# Sch1.net
KiCad netlist of a schematic drawn in Altium Designer
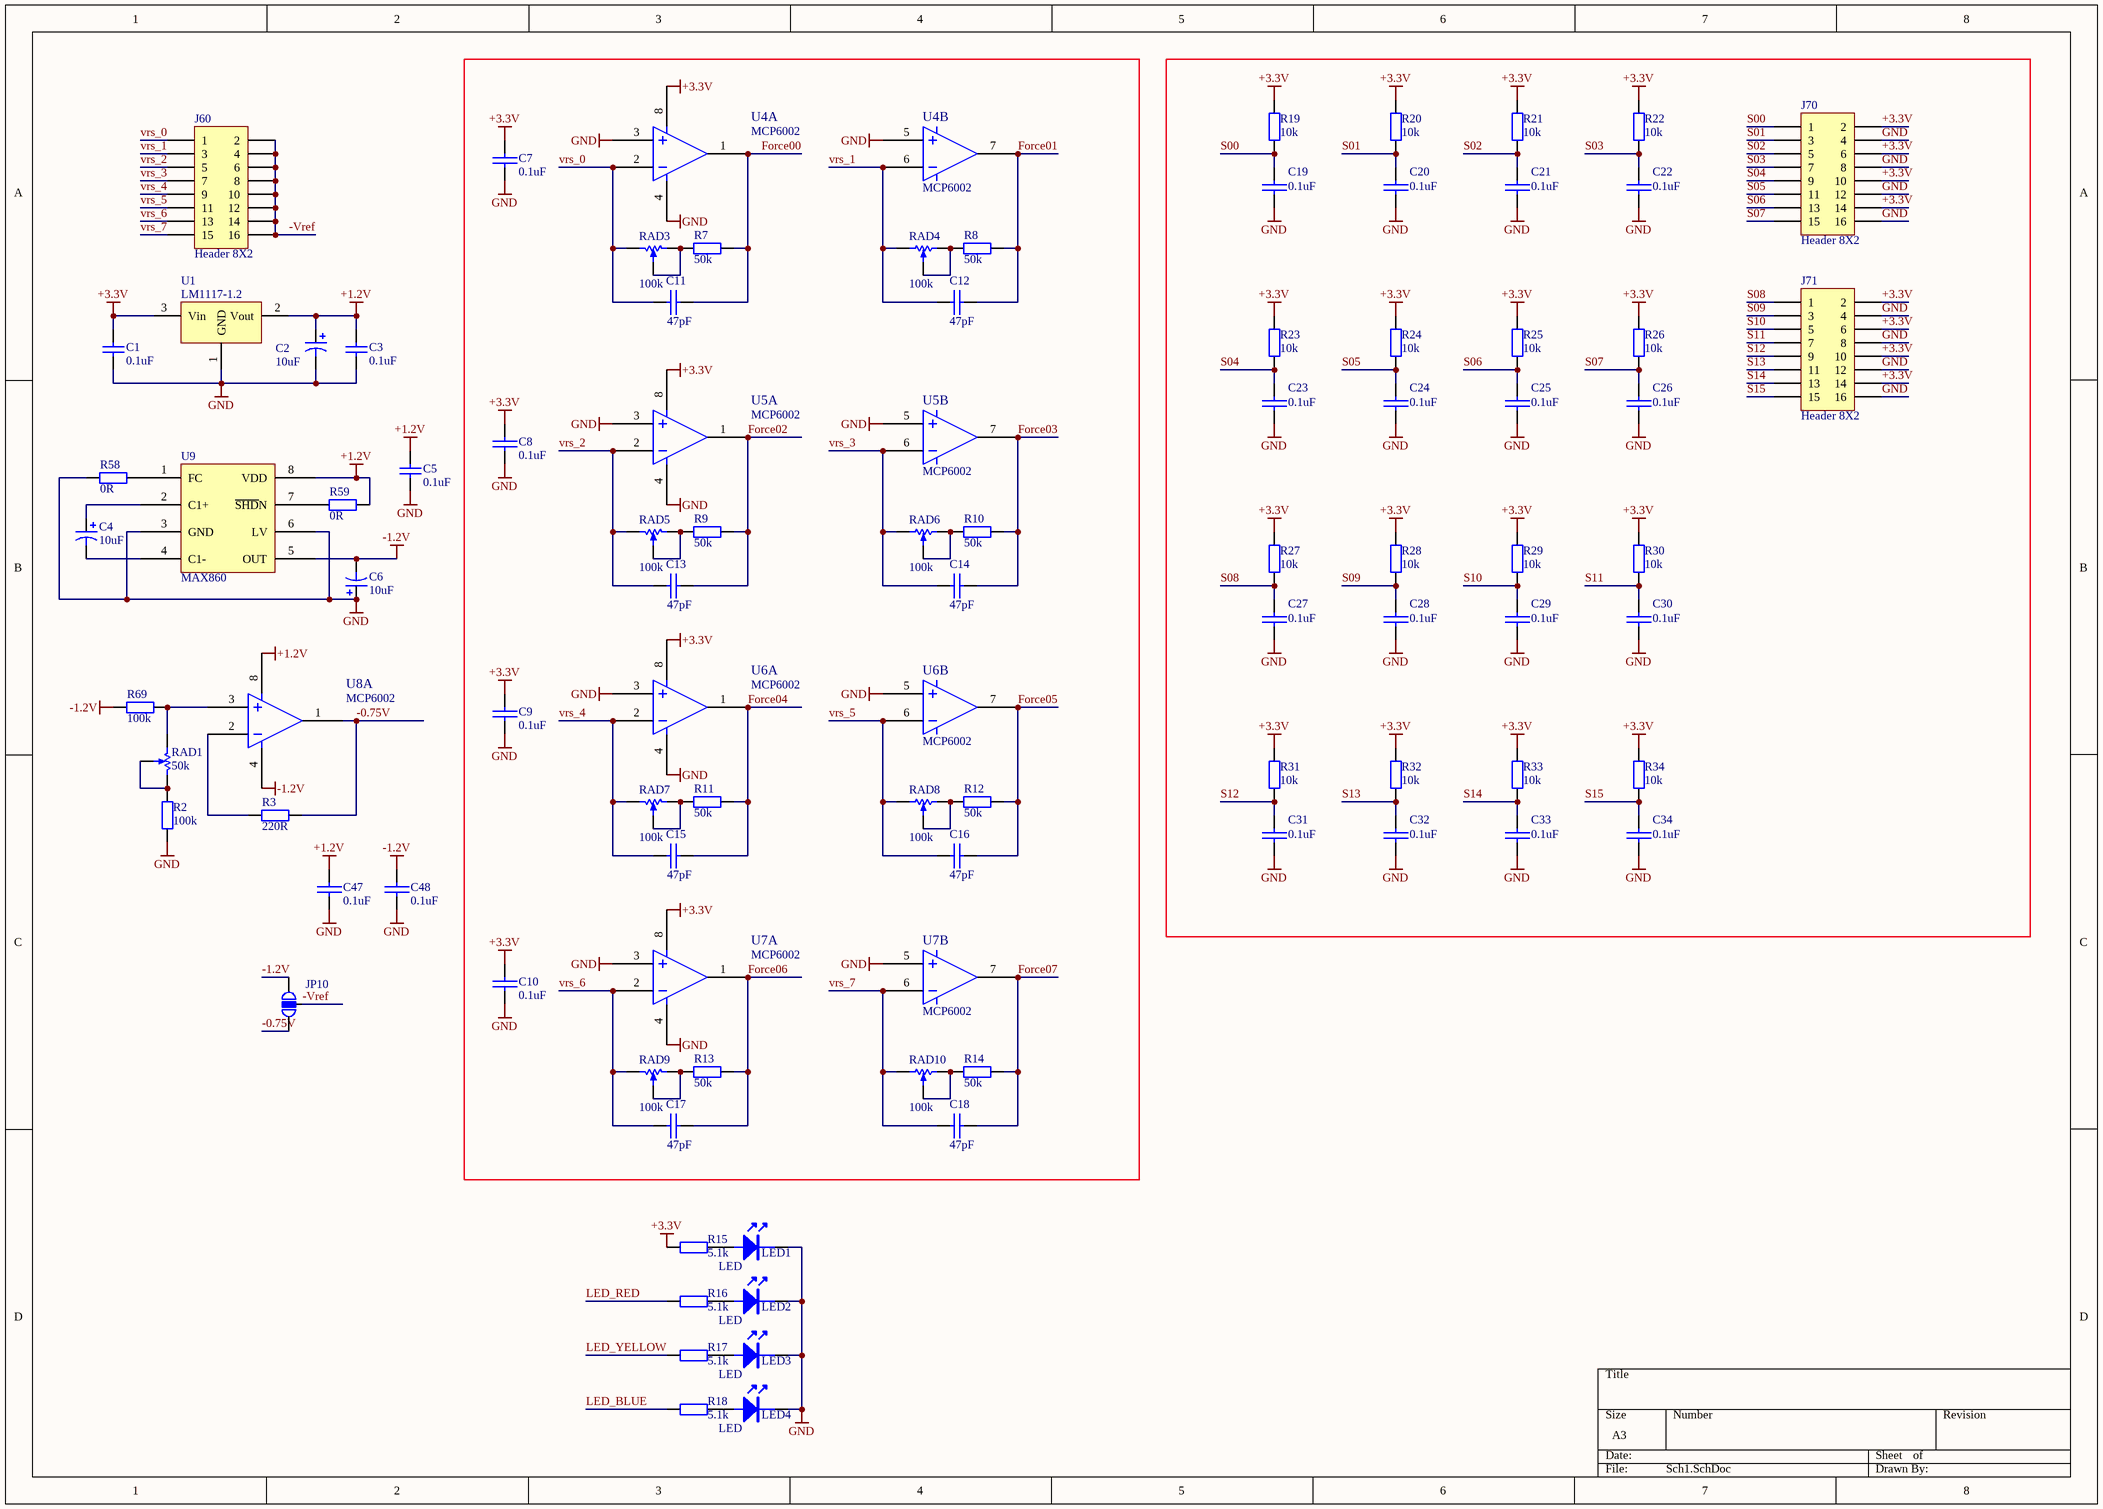
[diagram p0: Sch1.SchDoc]

(export (version "E")
  (design (tool "Eeschema 10.0.6"))
  (components
    (comp (ref "C1")
      (value "0.1uF")
      (footprint "CC0603")
      (description "贴片电容")
      (fields (field (name "Comment") "0603-50V-0.1uF"))
      (libsource (lib "Miscellaneous Devices") (part "Cap"))
    )
    (comp (ref "C2")
      (value "10uF")
      (footprint "SMD-EC-F5")
      (description "贴片铝电解电容")
      (fields (field (name "Comment") "CD-50V-10uF-F5(SMD)"))
      (libsource (lib "Miscellaneous Devices") (part "Cap Pol1"))
    )
    (comp (ref "C3")
      (value "0.1uF")
      (footprint "CC0603")
      (description "贴片电容")
      (fields (field (name "Comment") "0603-50V-0.1uF"))
      (libsource (lib "Miscellaneous Devices") (part "Cap"))
    )
    (comp (ref "C4")
      (value "10uF")
      (footprint "SMD-EC-F5")
      (description "贴片铝电解电容")
      (fields (field (name "Comment") "CD-50V-10uF-F5(SMD)"))
      (libsource (lib "Miscellaneous Devices") (part "Cap Pol1"))
    )
    (comp (ref "C5")
      (value "0.1uF")
      (footprint "CC0603")
      (description "贴片电容")
      (fields (field (name "Comment") "0603-50V-0.1uF"))
      (libsource (lib "Miscellaneous Devices") (part "Cap"))
    )
    (comp (ref "C6")
      (value "10uF")
      (footprint "SMD-EC-F5")
      (description "贴片铝电解电容")
      (fields (field (name "Comment") "CD-50V-10uF-F5(SMD)"))
      (libsource (lib "Miscellaneous Devices") (part "Cap Pol1"))
    )
    (comp (ref "C7")
      (value "0.1uF")
      (footprint "CC0603")
      (description "贴片电容")
      (fields (field (name "Comment") "0603-50V-0.1uF"))
      (libsource (lib "*") (part "CAP"))
    )
    (comp (ref "C8")
      (value "0.1uF")
      (footprint "CC0603")
      (description "贴片电容")
      (fields (field (name "Comment") "0603-50V-0.1uF"))
      (libsource (lib "*") (part "CAP"))
    )
    (comp (ref "C9")
      (value "0.1uF")
      (footprint "CC0603")
      (description "贴片电容")
      (fields (field (name "Comment") "0603-50V-0.1uF"))
      (libsource (lib "*") (part "CAP"))
    )
    (comp (ref "C10")
      (value "0.1uF")
      (footprint "CC0603")
      (description "贴片电容")
      (fields (field (name "Comment") "0603-50V-0.1uF"))
      (libsource (lib "*") (part "CAP"))
    )
    (comp (ref "C11")
      (value "47pF")
      (footprint "CC0603")
      (description "贴片电容")
      (fields (field (name "Comment") "0603-50V-47pF"))
      (libsource (lib "*") (part "CAP"))
    )
    (comp (ref "C12")
      (value "47pF")
      (footprint "CC0603")
      (description "贴片电容")
      (fields (field (name "Comment") "0603-50V-47pF"))
      (libsource (lib "*") (part "CAP"))
    )
    (comp (ref "C13")
      (value "47pF")
      (footprint "CC0603")
      (description "贴片电容")
      (fields (field (name "Comment") "0603-50V-47pF"))
      (libsource (lib "*") (part "CAP"))
    )
    (comp (ref "C14")
      (value "47pF")
      (footprint "CC0603")
      (description "贴片电容")
      (fields (field (name "Comment") "0603-50V-47pF"))
      (libsource (lib "*") (part "CAP"))
    )
    (comp (ref "C15")
      (value "47pF")
      (footprint "CC0603")
      (description "贴片电容")
      (fields (field (name "Comment") "0603-50V-47pF"))
      (libsource (lib "*") (part "CAP"))
    )
    (comp (ref "C16")
      (value "47pF")
      (footprint "CC0603")
      (description "贴片电容")
      (fields (field (name "Comment") "0603-50V-47pF"))
      (libsource (lib "*") (part "CAP"))
    )
    (comp (ref "C17")
      (value "47pF")
      (footprint "CC0603")
      (description "贴片电容")
      (fields (field (name "Comment") "0603-50V-47pF"))
      (libsource (lib "*") (part "CAP"))
    )
    (comp (ref "C18")
      (value "47pF")
      (footprint "CC0603")
      (description "贴片电容")
      (fields (field (name "Comment") "0603-50V-47pF"))
      (libsource (lib "*") (part "CAP"))
    )
    (comp (ref "C19")
      (value "0.1uF")
      (footprint "CC0603")
      (description "贴片电容")
      (fields (field (name "Comment") "0603-50V-0.1uF"))
      (libsource (lib "*") (part "CAP"))
    )
    (comp (ref "C20")
      (value "0.1uF")
      (footprint "CC0603")
      (description "贴片电容")
      (fields (field (name "Comment") "0603-50V-0.1uF"))
      (libsource (lib "*") (part "CAP"))
    )
    (comp (ref "C21")
      (value "0.1uF")
      (footprint "CC0603")
      (description "贴片电容")
      (fields (field (name "Comment") "0603-50V-0.1uF"))
      (libsource (lib "*") (part "CAP"))
    )
    (comp (ref "C22")
      (value "0.1uF")
      (footprint "CC0603")
      (description "贴片电容")
      (fields (field (name "Comment") "0603-50V-0.1uF"))
      (libsource (lib "*") (part "CAP"))
    )
    (comp (ref "C23")
      (value "0.1uF")
      (footprint "CC0603")
      (description "贴片电容")
      (fields (field (name "Comment") "0603-50V-0.1uF"))
      (libsource (lib "*") (part "CAP"))
    )
    (comp (ref "C24")
      (value "0.1uF")
      (footprint "CC0603")
      (description "贴片电容")
      (fields (field (name "Comment") "0603-50V-0.1uF"))
      (libsource (lib "*") (part "CAP"))
    )
    (comp (ref "C25")
      (value "0.1uF")
      (footprint "CC0603")
      (description "贴片电容")
      (fields (field (name "Comment") "0603-50V-0.1uF"))
      (libsource (lib "*") (part "CAP"))
    )
    (comp (ref "C26")
      (value "0.1uF")
      (footprint "CC0603")
      (description "贴片电容")
      (fields (field (name "Comment") "0603-50V-0.1uF"))
      (libsource (lib "*") (part "CAP"))
    )
    (comp (ref "C27")
      (value "0.1uF")
      (footprint "CC0603")
      (description "贴片电容")
      (fields (field (name "Comment") "0603-50V-0.1uF"))
      (libsource (lib "*") (part "CAP"))
    )
    (comp (ref "C28")
      (value "0.1uF")
      (footprint "CC0603")
      (description "贴片电容")
      (fields (field (name "Comment") "0603-50V-0.1uF"))
      (libsource (lib "*") (part "CAP"))
    )
    (comp (ref "C29")
      (value "0.1uF")
      (footprint "CC0603")
      (description "贴片电容")
      (fields (field (name "Comment") "0603-50V-0.1uF"))
      (libsource (lib "*") (part "CAP"))
    )
    (comp (ref "C30")
      (value "0.1uF")
      (footprint "CC0603")
      (description "贴片电容")
      (fields (field (name "Comment") "0603-50V-0.1uF"))
      (libsource (lib "*") (part "CAP"))
    )
    (comp (ref "C31")
      (value "0.1uF")
      (footprint "CC0603")
      (description "贴片电容")
      (fields (field (name "Comment") "0603-50V-0.1uF"))
      (libsource (lib "*") (part "CAP"))
    )
    (comp (ref "C32")
      (value "0.1uF")
      (footprint "CC0603")
      (description "贴片电容")
      (fields (field (name "Comment") "0603-50V-0.1uF"))
      (libsource (lib "*") (part "CAP"))
    )
    (comp (ref "C33")
      (value "0.1uF")
      (footprint "CC0603")
      (description "贴片电容")
      (fields (field (name "Comment") "0603-50V-0.1uF"))
      (libsource (lib "*") (part "CAP"))
    )
    (comp (ref "C34")
      (value "0.1uF")
      (footprint "CC0603")
      (description "贴片电容")
      (fields (field (name "Comment") "0603-50V-0.1uF"))
      (libsource (lib "*") (part "CAP"))
    )
    (comp (ref "C47")
      (value "0.1uF")
      (footprint "CC0603")
      (description "贴片电容")
      (fields (field (name "Comment") "0603-50V-0.1uF"))
      (libsource (lib "*") (part "CAP"))
    )
    (comp (ref "C48")
      (value "0.1uF")
      (footprint "CC0603")
      (description "贴片电容")
      (fields (field (name "Comment") "0603-50V-0.1uF"))
      (libsource (lib "*") (part "CAP"))
    )
    (comp (ref "J60")
      (value "Header 8X2")
      (footprint "HDR2X8")
      (description "排针")
      (libsource (lib "Miscellaneous Connectors") (part "Header 8X2"))
    )
    (comp (ref "J70")
      (value "Header 8X2")
      (footprint "HDR2X8")
      (description "排针")
      (libsource (lib "Miscellaneous Connectors") (part "Header 8X2"))
    )
    (comp (ref "J71")
      (value "Header 8X2")
      (footprint "HDR2X8")
      (description "排针")
      (libsource (lib "Miscellaneous Connectors") (part "Header 8X2"))
    )
    (comp (ref "JP10") (value "Jumper") (footprint "HDR1X3") (libsource (lib "SHIELD_3") (part "Bell")))
    (comp (ref "LED1")
      (value "LED")
      (footprint "LED-R3")
      (description "发光二极管")
      (fields (field (name "Comment") "LED-φ3(翠绿)"))
      (libsource (lib "*") (part "LED"))
    )
    (comp (ref "LED2")
      (value "LED")
      (footprint "LED-R3")
      (description "发光二极管")
      (fields (field (name "Comment") "LED-φ3(红)"))
      (libsource (lib "*") (part "LED"))
    )
    (comp (ref "LED3")
      (value "LED")
      (footprint "LED-R3")
      (description "发光二极管")
      (fields (field (name "Comment") "LED-φ3(黄)"))
      (libsource (lib "*") (part "LED"))
    )
    (comp (ref "LED4")
      (value "LED")
      (footprint "LED-R3")
      (description "发光二极管")
      (fields (field (name "Comment") "LED-φ3(蓝)"))
      (libsource (lib "*") (part "LED"))
    )
    (comp (ref "R2")
      (value "100k")
      (footprint "0603")
      (description "贴片电阻")
      (fields (field (name "Comment") "0603-100kΩ±1％"))
      (libsource (lib "") (part "Res2_3"))
    )
    (comp (ref "R3")
      (value "220R")
      (footprint "0603")
      (description "贴片电阻")
      (fields (field (name "Comment") "0603-220Ω±1％"))
      (libsource (lib "Miscellaneous Devices") (part "Res2"))
    )
    (comp (ref "R7")
      (value "50k")
      (footprint "0603")
      (description "贴片电阻")
      (fields (field (name "Comment") "0603-50kΩ±1％"))
      (libsource (lib "Miscellaneous Devices") (part "Res2"))
    )
    (comp (ref "R8")
      (value "50k")
      (footprint "0603")
      (description "贴片电阻")
      (fields (field (name "Comment") "0603-50kΩ±1％"))
      (libsource (lib "") (part "Res2_2"))
    )
    (comp (ref "R9")
      (value "50k")
      (footprint "0603")
      (description "贴片电阻")
      (fields (field (name "Comment") "0603-50kΩ±1％"))
      (libsource (lib "Miscellaneous Devices") (part "Res2"))
    )
    (comp (ref "R10")
      (value "50k")
      (footprint "0603")
      (description "贴片电阻")
      (fields (field (name "Comment") "0603-50kΩ±1％"))
      (libsource (lib "") (part "Res2_2"))
    )
    (comp (ref "R11")
      (value "50k")
      (footprint "0603")
      (description "贴片电阻")
      (fields (field (name "Comment") "0603-50kΩ±1％"))
      (libsource (lib "Miscellaneous Devices") (part "Res2"))
    )
    (comp (ref "R12")
      (value "50k")
      (footprint "0603")
      (description "贴片电阻")
      (fields (field (name "Comment") "0603-50kΩ±1％"))
      (libsource (lib "") (part "Res2_2"))
    )
    (comp (ref "R13")
      (value "50k")
      (footprint "0603")
      (description "贴片电阻")
      (fields (field (name "Comment") "0603-50kΩ±1％"))
      (libsource (lib "Miscellaneous Devices") (part "Res2"))
    )
    (comp (ref "R14")
      (value "50k")
      (footprint "0603")
      (description "贴片电阻")
      (fields (field (name "Comment") "0603-50kΩ±1％"))
      (libsource (lib "") (part "Res2_2"))
    )
    (comp (ref "R15")
      (value "5.1k")
      (footprint "0603")
      (description "贴片电阻器")
      (fields (field (name "Comment") "0603-5.1kΩ±1％"))
      (libsource (lib "") (part "Res2_2"))
    )
    (comp (ref "R16")
      (value "5.1k")
      (footprint "0603")
      (description "贴片电阻器")
      (fields (field (name "Comment") "0603-5.1kΩ±1％"))
      (libsource (lib "") (part "Res2_2"))
    )
    (comp (ref "R17")
      (value "5.1k")
      (footprint "0603")
      (description "贴片电阻器")
      (fields (field (name "Comment") "0603-5.1kΩ±1％"))
      (libsource (lib "") (part "Res2_2"))
    )
    (comp (ref "R18")
      (value "5.1k")
      (footprint "0603")
      (description "贴片电阻器")
      (fields (field (name "Comment") "0603-5.1kΩ±1％"))
      (libsource (lib "") (part "Res2_2"))
    )
    (comp (ref "R19")
      (value "10k")
      (footprint "0603")
      (description "贴片电阻")
      (fields (field (name "Comment") "0603-10kΩ±1％"))
      (libsource (lib "") (part "Res2_1"))
    )
    (comp (ref "R20")
      (value "10k")
      (footprint "0603")
      (description "贴片电阻")
      (fields (field (name "Comment") "0603-10kΩ±1％"))
      (libsource (lib "") (part "Res2_1"))
    )
    (comp (ref "R21")
      (value "10k")
      (footprint "0603")
      (description "贴片电阻")
      (fields (field (name "Comment") "0603-10kΩ±1％"))
      (libsource (lib "") (part "Res2_1"))
    )
    (comp (ref "R22")
      (value "10k")
      (footprint "0603")
      (description "贴片电阻")
      (fields (field (name "Comment") "0603-10kΩ±1％"))
      (libsource (lib "") (part "Res2_1"))
    )
    (comp (ref "R23")
      (value "10k")
      (footprint "0603")
      (description "贴片电阻")
      (fields (field (name "Comment") "0603-10kΩ±1％"))
      (libsource (lib "") (part "Res2_1"))
    )
    (comp (ref "R24")
      (value "10k")
      (footprint "0603")
      (description "贴片电阻")
      (fields (field (name "Comment") "0603-10kΩ±1％"))
      (libsource (lib "") (part "Res2_1"))
    )
    (comp (ref "R25")
      (value "10k")
      (footprint "0603")
      (description "贴片电阻")
      (fields (field (name "Comment") "0603-10kΩ±1％"))
      (libsource (lib "") (part "Res2_1"))
    )
    (comp (ref "R26")
      (value "10k")
      (footprint "0603")
      (description "贴片电阻")
      (fields (field (name "Comment") "0603-10kΩ±1％"))
      (libsource (lib "") (part "Res2_1"))
    )
    (comp (ref "R27")
      (value "10k")
      (footprint "0603")
      (description "贴片电阻")
      (fields (field (name "Comment") "0603-10kΩ±1％"))
      (libsource (lib "") (part "Res2_1"))
    )
    (comp (ref "R28")
      (value "10k")
      (footprint "0603")
      (description "贴片电阻")
      (fields (field (name "Comment") "0603-10kΩ±1％"))
      (libsource (lib "") (part "Res2_1"))
    )
    (comp (ref "R29")
      (value "10k")
      (footprint "0603")
      (description "贴片电阻")
      (fields (field (name "Comment") "0603-10kΩ±1％"))
      (libsource (lib "") (part "Res2_1"))
    )
    (comp (ref "R30")
      (value "10k")
      (footprint "0603")
      (description "贴片电阻")
      (fields (field (name "Comment") "0603-10kΩ±1％"))
      (libsource (lib "") (part "Res2_1"))
    )
    (comp (ref "R31")
      (value "10k")
      (footprint "0603")
      (description "贴片电阻")
      (fields (field (name "Comment") "0603-10kΩ±1％"))
      (libsource (lib "") (part "Res2_1"))
    )
    (comp (ref "R32")
      (value "10k")
      (footprint "0603")
      (description "贴片电阻")
      (fields (field (name "Comment") "0603-10kΩ±1％"))
      (libsource (lib "") (part "Res2_1"))
    )
    (comp (ref "R33")
      (value "10k")
      (footprint "0603")
      (description "贴片电阻")
      (fields (field (name "Comment") "0603-10kΩ±1％"))
      (libsource (lib "") (part "Res2_1"))
    )
    (comp (ref "R34")
      (value "10k")
      (footprint "0603")
      (description "贴片电阻")
      (fields (field (name "Comment") "0603-10kΩ±1％"))
      (libsource (lib "") (part "Res2_1"))
    )
    (comp (ref "R58")
      (value "0R")
      (footprint "0603")
      (description "贴片电阻")
      (fields (field (name "Comment") "0603-0Ω±1％"))
      (libsource (lib "Miscellaneous Devices") (part "Res2"))
    )
    (comp (ref "R59")
      (value "0R")
      (footprint "0603")
      (description "贴片电阻")
      (fields (field (name "Comment") "0603-0Ω±1％"))
      (libsource (lib "Miscellaneous Devices") (part "Res2"))
    )
    (comp (ref "R69")
      (value "100k")
      (footprint "0603")
      (description "贴片电阻")
      (fields (field (name "Comment") "0603-100kΩ±1％"))
      (libsource (lib "") (part "Res2_1"))
    )
    (comp (ref "RAD1")
      (value "50k")
      (footprint "3224W")
      (description "贴片电位器")
      (fields (field (name "Comment") "3224W-50k"))
      (libsource (lib "Miscellaneous Devices") (part "RPot SM"))
    )
    (comp (ref "RAD3")
      (value "100k")
      (footprint "3224W")
      (description "贴片电位器")
      (fields (field (name "Comment") "3224W-100k"))
      (libsource (lib "Miscellaneous Devices") (part "RPot SM"))
    )
    (comp (ref "RAD4")
      (value "100k")
      (footprint "3224W")
      (description "贴片电位器")
      (fields (field (name "Comment") "3224W-100k"))
      (libsource (lib "Miscellaneous Devices") (part "RPot SM"))
    )
    (comp (ref "RAD5")
      (value "100k")
      (footprint "3224W")
      (description "贴片电位器")
      (fields (field (name "Comment") "3224W-100k"))
      (libsource (lib "Miscellaneous Devices") (part "RPot SM"))
    )
    (comp (ref "RAD6")
      (value "100k")
      (footprint "3224W")
      (description "贴片电位器")
      (fields (field (name "Comment") "3224W-100k"))
      (libsource (lib "Miscellaneous Devices") (part "RPot SM"))
    )
    (comp (ref "RAD7")
      (value "100k")
      (footprint "3224W")
      (description "贴片电位器")
      (fields (field (name "Comment") "3224W-100k"))
      (libsource (lib "Miscellaneous Devices") (part "RPot SM"))
    )
    (comp (ref "RAD8")
      (value "100k")
      (footprint "3224W")
      (description "贴片电位器")
      (fields (field (name "Comment") "3224W-100k"))
      (libsource (lib "Miscellaneous Devices") (part "RPot SM"))
    )
    (comp (ref "RAD9")
      (value "100k")
      (footprint "3224W")
      (description "贴片电位器")
      (fields (field (name "Comment") "3224W-100k"))
      (libsource (lib "Miscellaneous Devices") (part "RPot SM"))
    )
    (comp (ref "RAD10")
      (value "100k")
      (footprint "3224W")
      (description "贴片电位器")
      (fields (field (name "Comment") "3224W-100k"))
      (libsource (lib "Miscellaneous Devices") (part "RPot SM"))
    )
    (comp (ref "U1")
      (value "LM1117-1.2")
      (footprint "SOT223")
      (description "三端稳压器")
      (fields (field (name "Comment") "LM1117GS-1.2"))
      (libsource (lib "*") (part "78M05"))
    )
    (comp (ref "U4")
      (value "MCP6002")
      (footprint "SO-8")
      (description "集成电路")
      (libsource (lib "*") (part "1458"))
    )
    (comp (ref "U5")
      (value "MCP6002")
      (footprint "SO-8")
      (description "集成电路")
      (libsource (lib "*") (part "1458"))
    )
    (comp (ref "U6")
      (value "MCP6002")
      (footprint "SO-8")
      (description "集成电路")
      (libsource (lib "*") (part "1458"))
    )
    (comp (ref "U7")
      (value "MCP6002")
      (footprint "SO-8")
      (description "集成电路")
      (libsource (lib "*") (part "1458"))
    )
    (comp (ref "U8")
      (value "MCP6002")
      (footprint "SO-8")
      (description "集成电路")
      (libsource (lib "*") (part "1458"))
    )
    (comp (ref "U9")
      (value "MAX860")
      (footprint "SO-8")
      (description "集成电路")
      (fields (field (name "Comment") "max860"))
      (libsource (lib "Schlib1") (part "max860"))
    )
  )
  (nets
    (net (code "1") (name "+1.2V") (class "Default")
      (node (ref "C2") (pin "1") (pinfunction "1_1") (pintype "passive"))
      (node (ref "C3") (pin "2") (pinfunction "2_2") (pintype "passive"))
      (node (ref "C47") (pin "2") (pinfunction "2_2") (pintype "passive"))
      (node (ref "C5") (pin "2") (pinfunction "2_2") (pintype "passive"))
      (node (ref "R59") (pin "2") (pinfunction "2_2") (pintype "passive"))
      (node (ref "U1") (pin "2") (pinfunction "Vout_2") (pintype "passive"))
      (node (ref "U8") (pin "8") (pintype "passive"))
      (node (ref "U9") (pin "8") (pinfunction "VDD_8") (pintype "passive"))
    )
    (net (code "2") (name "+3.3V") (class "Default")
      (node (ref "C1") (pin "2") (pinfunction "2_2") (pintype "passive"))
      (node (ref "C10") (pin "2") (pinfunction "2_2") (pintype "passive"))
      (node (ref "C7") (pin "2") (pinfunction "2_2") (pintype "passive"))
      (node (ref "C8") (pin "2") (pinfunction "2_2") (pintype "passive"))
      (node (ref "C9") (pin "2") (pinfunction "2_2") (pintype "passive"))
      (node (ref "J70") (pin "10") (pinfunction "10_10") (pintype "passive"))
      (node (ref "J70") (pin "14") (pinfunction "14_14") (pintype "passive"))
      (node (ref "J70") (pin "2") (pinfunction "2_2") (pintype "passive"))
      (node (ref "J70") (pin "6") (pinfunction "6_6") (pintype "passive"))
      (node (ref "J71") (pin "10") (pinfunction "10_10") (pintype "passive"))
      (node (ref "J71") (pin "14") (pinfunction "14_14") (pintype "passive"))
      (node (ref "J71") (pin "2") (pinfunction "2_2") (pintype "passive"))
      (node (ref "J71") (pin "6") (pinfunction "6_6") (pintype "passive"))
      (node (ref "R15") (pin "2") (pinfunction "2_2") (pintype "passive"))
      (node (ref "R19") (pin "1") (pinfunction "1_1") (pintype "passive"))
      (node (ref "R20") (pin "1") (pinfunction "1_1") (pintype "passive"))
      (node (ref "R21") (pin "1") (pinfunction "1_1") (pintype "passive"))
      (node (ref "R22") (pin "1") (pinfunction "1_1") (pintype "passive"))
      (node (ref "R23") (pin "1") (pinfunction "1_1") (pintype "passive"))
      (node (ref "R24") (pin "1") (pinfunction "1_1") (pintype "passive"))
      (node (ref "R25") (pin "1") (pinfunction "1_1") (pintype "passive"))
      (node (ref "R26") (pin "1") (pinfunction "1_1") (pintype "passive"))
      (node (ref "R27") (pin "1") (pinfunction "1_1") (pintype "passive"))
      (node (ref "R28") (pin "1") (pinfunction "1_1") (pintype "passive"))
      (node (ref "R29") (pin "1") (pinfunction "1_1") (pintype "passive"))
      (node (ref "R30") (pin "1") (pinfunction "1_1") (pintype "passive"))
      (node (ref "R31") (pin "1") (pinfunction "1_1") (pintype "passive"))
      (node (ref "R32") (pin "1") (pinfunction "1_1") (pintype "passive"))
      (node (ref "R33") (pin "1") (pinfunction "1_1") (pintype "passive"))
      (node (ref "R34") (pin "1") (pinfunction "1_1") (pintype "passive"))
      (node (ref "U1") (pin "3") (pinfunction "Vin_3") (pintype "passive"))
      (node (ref "U4") (pin "8") (pintype "passive"))
      (node (ref "U5") (pin "8") (pintype "passive"))
      (node (ref "U6") (pin "8") (pintype "passive"))
      (node (ref "U7") (pin "8") (pintype "passive"))
    )
    (net (code "3") (name "-1.2V") (class "Default")
      (node (ref "C48") (pin "2") (pinfunction "2_2") (pintype "passive"))
      (node (ref "C6") (pin "2") (pinfunction "2_2") (pintype "passive"))
      (node (ref "JP10") (pin "1") (pinfunction "A_1") (pintype "passive"))
      (node (ref "R69") (pin "2") (pinfunction "2_2") (pintype "passive"))
      (node (ref "U8") (pin "4") (pintype "passive"))
      (node (ref "U9") (pin "5") (pinfunction "OUT_5") (pintype "passive"))
    )
    (net (code "4") (name "/-0.75V") (class "Default")
      (node (ref "JP10") (pin "3") (pinfunction "B_3") (pintype "passive"))
      (node (ref "R3") (pin "2") (pinfunction "2_2") (pintype "passive"))
      (node (ref "U8") (pin "1") (pintype "passive"))
    )
    (net (code "5") (name "/-Vref") (class "Default")
      (node (ref "J60") (pin "10") (pinfunction "10_10") (pintype "passive"))
      (node (ref "J60") (pin "12") (pinfunction "12_12") (pintype "passive"))
      (node (ref "J60") (pin "14") (pinfunction "14_14") (pintype "passive"))
      (node (ref "J60") (pin "16") (pinfunction "16_16") (pintype "passive"))
      (node (ref "J60") (pin "2") (pinfunction "2_2") (pintype "passive"))
      (node (ref "J60") (pin "4") (pinfunction "4_4") (pintype "passive"))
      (node (ref "J60") (pin "6") (pinfunction "6_6") (pintype "passive"))
      (node (ref "J60") (pin "8") (pinfunction "8_8") (pintype "passive"))
      (node (ref "JP10") (pin "2") (pinfunction "B_2") (pintype "passive"))
    )
    (net (code "6") (name "/Force00") (class "Default")
      (node (ref "C11") (pin "1") (pinfunction "1_1") (pintype "passive"))
      (node (ref "R7") (pin "2") (pinfunction "2_2") (pintype "passive"))
      (node (ref "U4") (pin "1") (pintype "passive"))
    )
    (net (code "7") (name "/Force01") (class "Default")
      (node (ref "C12") (pin "1") (pinfunction "1_1") (pintype "passive"))
      (node (ref "R8") (pin "1") (pinfunction "1_1") (pintype "passive"))
      (node (ref "U4") (pin "7") (pintype "passive"))
    )
    (net (code "8") (name "/Force02") (class "Default")
      (node (ref "C13") (pin "1") (pinfunction "1_1") (pintype "passive"))
      (node (ref "R9") (pin "2") (pinfunction "2_2") (pintype "passive"))
      (node (ref "U5") (pin "1") (pintype "passive"))
    )
    (net (code "9") (name "/Force03") (class "Default")
      (node (ref "C14") (pin "1") (pinfunction "1_1") (pintype "passive"))
      (node (ref "R10") (pin "1") (pinfunction "1_1") (pintype "passive"))
      (node (ref "U5") (pin "7") (pintype "passive"))
    )
    (net (code "10") (name "/Force04") (class "Default")
      (node (ref "C15") (pin "1") (pinfunction "1_1") (pintype "passive"))
      (node (ref "R11") (pin "2") (pinfunction "2_2") (pintype "passive"))
      (node (ref "U6") (pin "1") (pintype "passive"))
    )
    (net (code "11") (name "/Force05") (class "Default")
      (node (ref "C16") (pin "1") (pinfunction "1_1") (pintype "passive"))
      (node (ref "R12") (pin "1") (pinfunction "1_1") (pintype "passive"))
      (node (ref "U6") (pin "7") (pintype "passive"))
    )
    (net (code "12") (name "/Force06") (class "Default")
      (node (ref "C17") (pin "1") (pinfunction "1_1") (pintype "passive"))
      (node (ref "R13") (pin "2") (pinfunction "2_2") (pintype "passive"))
      (node (ref "U7") (pin "1") (pintype "passive"))
    )
    (net (code "13") (name "/Force07") (class "Default")
      (node (ref "C18") (pin "1") (pinfunction "1_1") (pintype "passive"))
      (node (ref "R14") (pin "1") (pinfunction "1_1") (pintype "passive"))
      (node (ref "U7") (pin "7") (pintype "passive"))
    )
    (net (code "14") (name "/LED_BLUE") (class "Default")
      (node (ref "R18") (pin "2") (pinfunction "2_2") (pintype "passive"))
    )
    (net (code "15") (name "/LED_RED") (class "Default")
      (node (ref "R16") (pin "2") (pinfunction "2_2") (pintype "passive"))
    )
    (net (code "16") (name "/LED_YELLOW") (class "Default")
      (node (ref "R17") (pin "2") (pinfunction "2_2") (pintype "passive"))
    )
    (net (code "17") (name "/S00") (class "Default")
      (node (ref "C19") (pin "1") (pinfunction "1_1") (pintype "passive"))
      (node (ref "J70") (pin "1") (pinfunction "1_1") (pintype "passive"))
      (node (ref "R19") (pin "2") (pinfunction "2_2") (pintype "passive"))
    )
    (net (code "18") (name "/S01") (class "Default")
      (node (ref "C20") (pin "1") (pinfunction "1_1") (pintype "passive"))
      (node (ref "J70") (pin "3") (pinfunction "3_3") (pintype "passive"))
      (node (ref "R20") (pin "2") (pinfunction "2_2") (pintype "passive"))
    )
    (net (code "19") (name "/S02") (class "Default")
      (node (ref "C21") (pin "1") (pinfunction "1_1") (pintype "passive"))
      (node (ref "J70") (pin "5") (pinfunction "5_5") (pintype "passive"))
      (node (ref "R21") (pin "2") (pinfunction "2_2") (pintype "passive"))
    )
    (net (code "20") (name "/S03") (class "Default")
      (node (ref "C22") (pin "1") (pinfunction "1_1") (pintype "passive"))
      (node (ref "J70") (pin "7") (pinfunction "7_7") (pintype "passive"))
      (node (ref "R22") (pin "2") (pinfunction "2_2") (pintype "passive"))
    )
    (net (code "21") (name "/S04") (class "Default")
      (node (ref "C23") (pin "1") (pinfunction "1_1") (pintype "passive"))
      (node (ref "J70") (pin "9") (pinfunction "9_9") (pintype "passive"))
      (node (ref "R23") (pin "2") (pinfunction "2_2") (pintype "passive"))
    )
    (net (code "22") (name "/S05") (class "Default")
      (node (ref "C24") (pin "1") (pinfunction "1_1") (pintype "passive"))
      (node (ref "J70") (pin "11") (pinfunction "11_11") (pintype "passive"))
      (node (ref "R24") (pin "2") (pinfunction "2_2") (pintype "passive"))
    )
    (net (code "23") (name "/S06") (class "Default")
      (node (ref "C25") (pin "1") (pinfunction "1_1") (pintype "passive"))
      (node (ref "J70") (pin "13") (pinfunction "13_13") (pintype "passive"))
      (node (ref "R25") (pin "2") (pinfunction "2_2") (pintype "passive"))
    )
    (net (code "24") (name "/S07") (class "Default")
      (node (ref "C26") (pin "1") (pinfunction "1_1") (pintype "passive"))
      (node (ref "J70") (pin "15") (pinfunction "15_15") (pintype "passive"))
      (node (ref "R26") (pin "2") (pinfunction "2_2") (pintype "passive"))
    )
    (net (code "25") (name "/S08") (class "Default")
      (node (ref "C27") (pin "1") (pinfunction "1_1") (pintype "passive"))
      (node (ref "J71") (pin "1") (pinfunction "1_1") (pintype "passive"))
      (node (ref "R27") (pin "2") (pinfunction "2_2") (pintype "passive"))
    )
    (net (code "26") (name "/S09") (class "Default")
      (node (ref "C28") (pin "1") (pinfunction "1_1") (pintype "passive"))
      (node (ref "J71") (pin "3") (pinfunction "3_3") (pintype "passive"))
      (node (ref "R28") (pin "2") (pinfunction "2_2") (pintype "passive"))
    )
    (net (code "27") (name "/S10") (class "Default")
      (node (ref "C29") (pin "1") (pinfunction "1_1") (pintype "passive"))
      (node (ref "J71") (pin "5") (pinfunction "5_5") (pintype "passive"))
      (node (ref "R29") (pin "2") (pinfunction "2_2") (pintype "passive"))
    )
    (net (code "28") (name "/S11") (class "Default")
      (node (ref "C30") (pin "1") (pinfunction "1_1") (pintype "passive"))
      (node (ref "J71") (pin "7") (pinfunction "7_7") (pintype "passive"))
      (node (ref "R30") (pin "2") (pinfunction "2_2") (pintype "passive"))
    )
    (net (code "29") (name "/S12") (class "Default")
      (node (ref "C31") (pin "1") (pinfunction "1_1") (pintype "passive"))
      (node (ref "J71") (pin "9") (pinfunction "9_9") (pintype "passive"))
      (node (ref "R31") (pin "2") (pinfunction "2_2") (pintype "passive"))
    )
    (net (code "30") (name "/S13") (class "Default")
      (node (ref "C32") (pin "1") (pinfunction "1_1") (pintype "passive"))
      (node (ref "J71") (pin "11") (pinfunction "11_11") (pintype "passive"))
      (node (ref "R32") (pin "2") (pinfunction "2_2") (pintype "passive"))
    )
    (net (code "31") (name "/S14") (class "Default")
      (node (ref "C33") (pin "1") (pinfunction "1_1") (pintype "passive"))
      (node (ref "J71") (pin "13") (pinfunction "13_13") (pintype "passive"))
      (node (ref "R33") (pin "2") (pinfunction "2_2") (pintype "passive"))
    )
    (net (code "32") (name "/S15") (class "Default")
      (node (ref "C34") (pin "1") (pinfunction "1_1") (pintype "passive"))
      (node (ref "J71") (pin "15") (pinfunction "15_15") (pintype "passive"))
      (node (ref "R34") (pin "2") (pinfunction "2_2") (pintype "passive"))
    )
    (net (code "33") (name "/vrs_0") (class "Default")
      (node (ref "C11") (pin "2") (pinfunction "2_2") (pintype "passive"))
      (node (ref "J60") (pin "1") (pinfunction "1_1") (pintype "passive"))
      (node (ref "RAD3") (pin "3") (pinfunction "CW_3") (pintype "passive"))
      (node (ref "U4") (pin "2") (pintype "passive"))
    )
    (net (code "34") (name "/vrs_1") (class "Default")
      (node (ref "C12") (pin "2") (pinfunction "2_2") (pintype "passive"))
      (node (ref "J60") (pin "3") (pinfunction "3_3") (pintype "passive"))
      (node (ref "RAD4") (pin "1") (pinfunction "CCW_1") (pintype "passive"))
      (node (ref "U4") (pin "6") (pintype "passive"))
    )
    (net (code "35") (name "/vrs_2") (class "Default")
      (node (ref "C13") (pin "2") (pinfunction "2_2") (pintype "passive"))
      (node (ref "J60") (pin "5") (pinfunction "5_5") (pintype "passive"))
      (node (ref "RAD5") (pin "3") (pinfunction "CW_3") (pintype "passive"))
      (node (ref "U5") (pin "2") (pintype "passive"))
    )
    (net (code "36") (name "/vrs_3") (class "Default")
      (node (ref "C14") (pin "2") (pinfunction "2_2") (pintype "passive"))
      (node (ref "J60") (pin "7") (pinfunction "7_7") (pintype "passive"))
      (node (ref "RAD6") (pin "1") (pinfunction "CCW_1") (pintype "passive"))
      (node (ref "U5") (pin "6") (pintype "passive"))
    )
    (net (code "37") (name "/vrs_4") (class "Default")
      (node (ref "C15") (pin "2") (pinfunction "2_2") (pintype "passive"))
      (node (ref "J60") (pin "9") (pinfunction "9_9") (pintype "passive"))
      (node (ref "RAD7") (pin "3") (pinfunction "CW_3") (pintype "passive"))
      (node (ref "U6") (pin "2") (pintype "passive"))
    )
    (net (code "38") (name "/vrs_5") (class "Default")
      (node (ref "C16") (pin "2") (pinfunction "2_2") (pintype "passive"))
      (node (ref "J60") (pin "11") (pinfunction "11_11") (pintype "passive"))
      (node (ref "RAD8") (pin "1") (pinfunction "CCW_1") (pintype "passive"))
      (node (ref "U6") (pin "6") (pintype "passive"))
    )
    (net (code "39") (name "/vrs_6") (class "Default")
      (node (ref "C17") (pin "2") (pinfunction "2_2") (pintype "passive"))
      (node (ref "J60") (pin "13") (pinfunction "13_13") (pintype "passive"))
      (node (ref "RAD9") (pin "3") (pinfunction "CW_3") (pintype "passive"))
      (node (ref "U7") (pin "2") (pintype "passive"))
    )
    (net (code "40") (name "/vrs_7") (class "Default")
      (node (ref "C18") (pin "2") (pinfunction "2_2") (pintype "passive"))
      (node (ref "J60") (pin "15") (pinfunction "15_15") (pintype "passive"))
      (node (ref "RAD10") (pin "1") (pinfunction "CCW_1") (pintype "passive"))
      (node (ref "U7") (pin "6") (pintype "passive"))
    )
    (net (code "41") (name "GND") (class "Default")
      (node (ref "C1") (pin "1") (pinfunction "1_1") (pintype "passive"))
      (node (ref "C10") (pin "1") (pinfunction "1_1") (pintype "passive"))
      (node (ref "C19") (pin "2") (pinfunction "2_2") (pintype "passive"))
      (node (ref "C2") (pin "2") (pinfunction "2_2") (pintype "passive"))
      (node (ref "C20") (pin "2") (pinfunction "2_2") (pintype "passive"))
      (node (ref "C21") (pin "2") (pinfunction "2_2") (pintype "passive"))
      (node (ref "C22") (pin "2") (pinfunction "2_2") (pintype "passive"))
      (node (ref "C23") (pin "2") (pinfunction "2_2") (pintype "passive"))
      (node (ref "C24") (pin "2") (pinfunction "2_2") (pintype "passive"))
      (node (ref "C25") (pin "2") (pinfunction "2_2") (pintype "passive"))
      (node (ref "C26") (pin "2") (pinfunction "2_2") (pintype "passive"))
      (node (ref "C27") (pin "2") (pinfunction "2_2") (pintype "passive"))
      (node (ref "C28") (pin "2") (pinfunction "2_2") (pintype "passive"))
      (node (ref "C29") (pin "2") (pinfunction "2_2") (pintype "passive"))
      (node (ref "C3") (pin "1") (pinfunction "1_1") (pintype "passive"))
      (node (ref "C30") (pin "2") (pinfunction "2_2") (pintype "passive"))
      (node (ref "C31") (pin "2") (pinfunction "2_2") (pintype "passive"))
      (node (ref "C32") (pin "2") (pinfunction "2_2") (pintype "passive"))
      (node (ref "C33") (pin "2") (pinfunction "2_2") (pintype "passive"))
      (node (ref "C34") (pin "2") (pinfunction "2_2") (pintype "passive"))
      (node (ref "C47") (pin "1") (pinfunction "1_1") (pintype "passive"))
      (node (ref "C48") (pin "1") (pinfunction "1_1") (pintype "passive"))
      (node (ref "C5") (pin "1") (pinfunction "1_1") (pintype "passive"))
      (node (ref "C6") (pin "1") (pinfunction "1_1") (pintype "passive"))
      (node (ref "C7") (pin "1") (pinfunction "1_1") (pintype "passive"))
      (node (ref "C8") (pin "1") (pinfunction "1_1") (pintype "passive"))
      (node (ref "C9") (pin "1") (pinfunction "1_1") (pintype "passive"))
      (node (ref "J70") (pin "12") (pinfunction "12_12") (pintype "passive"))
      (node (ref "J70") (pin "16") (pinfunction "16_16") (pintype "passive"))
      (node (ref "J70") (pin "4") (pinfunction "4_4") (pintype "passive"))
      (node (ref "J70") (pin "8") (pinfunction "8_8") (pintype "passive"))
      (node (ref "J71") (pin "12") (pinfunction "12_12") (pintype "passive"))
      (node (ref "J71") (pin "16") (pinfunction "16_16") (pintype "passive"))
      (node (ref "J71") (pin "4") (pinfunction "4_4") (pintype "passive"))
      (node (ref "J71") (pin "8") (pinfunction "8_8") (pintype "passive"))
      (node (ref "LED1") (pin "2") (pinfunction "2_2") (pintype "passive"))
      (node (ref "LED2") (pin "2") (pinfunction "2_2") (pintype "passive"))
      (node (ref "LED3") (pin "2") (pinfunction "2_2") (pintype "passive"))
      (node (ref "LED4") (pin "2") (pinfunction "2_2") (pintype "passive"))
      (node (ref "R2") (pin "1") (pinfunction "1_1") (pintype "passive"))
      (node (ref "R58") (pin "1") (pinfunction "1_1") (pintype "passive"))
      (node (ref "U1") (pin "1") (pinfunction "GND_1") (pintype "passive"))
      (node (ref "U4") (pin "3") (pintype "passive"))
      (node (ref "U4") (pin "4") (pintype "passive"))
      (node (ref "U4") (pin "5") (pintype "passive"))
      (node (ref "U5") (pin "3") (pintype "passive"))
      (node (ref "U5") (pin "4") (pintype "passive"))
      (node (ref "U5") (pin "5") (pintype "passive"))
      (node (ref "U6") (pin "3") (pintype "passive"))
      (node (ref "U6") (pin "4") (pintype "passive"))
      (node (ref "U6") (pin "5") (pintype "passive"))
      (node (ref "U7") (pin "3") (pintype "passive"))
      (node (ref "U7") (pin "4") (pintype "passive"))
      (node (ref "U7") (pin "5") (pintype "passive"))
      (node (ref "U9") (pin "3") (pinfunction "GND_3") (pintype "passive"))
      (node (ref "U9") (pin "6") (pinfunction "LV_6") (pintype "passive"))
    )
    (net (code "42") (name "Net-(LED1-Pad1)") (class "Default")
      (node (ref "LED1") (pin "1") (pinfunction "1_1") (pintype "passive"))
      (node (ref "R15") (pin "1") (pinfunction "1_1") (pintype "passive"))
    )
    (net (code "43") (name "Net-(LED2-Pad1)") (class "Default")
      (node (ref "LED2") (pin "1") (pinfunction "1_1") (pintype "passive"))
      (node (ref "R16") (pin "1") (pinfunction "1_1") (pintype "passive"))
    )
    (net (code "44") (name "Net-(LED3-Pad1)") (class "Default")
      (node (ref "LED3") (pin "1") (pinfunction "1_1") (pintype "passive"))
      (node (ref "R17") (pin "1") (pinfunction "1_1") (pintype "passive"))
    )
    (net (code "45") (name "Net-(LED4-Pad1)") (class "Default")
      (node (ref "LED4") (pin "1") (pinfunction "1_1") (pintype "passive"))
      (node (ref "R18") (pin "1") (pinfunction "1_1") (pintype "passive"))
    )
    (net (code "46") (name "Net-(R3-Pad1)") (class "Default")
      (node (ref "R3") (pin "1") (pinfunction "1_1") (pintype "passive"))
      (node (ref "U8") (pin "2") (pintype "passive"))
    )
    (net (code "47") (name "Net-(RAD1-CCW)") (class "Default")
      (node (ref "R2") (pin "2") (pinfunction "2_2") (pintype "passive"))
      (node (ref "RAD1") (pin "1") (pinfunction "CCW_1") (pintype "passive"))
      (node (ref "RAD1") (pin "2") (pinfunction "W_2") (pintype "passive"))
    )
    (net (code "48") (name "Net-(RAD1-CW)") (class "Default")
      (node (ref "R69") (pin "1") (pinfunction "1_1") (pintype "passive"))
      (node (ref "RAD1") (pin "3") (pinfunction "CW_3") (pintype "passive"))
      (node (ref "U8") (pin "3") (pintype "passive"))
    )
    (net (code "49") (name "Net-(RAD3-CCW)") (class "Default")
      (node (ref "R7") (pin "1") (pinfunction "1_1") (pintype "passive"))
      (node (ref "RAD3") (pin "1") (pinfunction "CCW_1") (pintype "passive"))
      (node (ref "RAD3") (pin "2") (pinfunction "W_2") (pintype "passive"))
    )
    (net (code "50") (name "Net-(RAD4-CW)") (class "Default")
      (node (ref "R8") (pin "2") (pinfunction "2_2") (pintype "passive"))
      (node (ref "RAD4") (pin "2") (pinfunction "W_2") (pintype "passive"))
      (node (ref "RAD4") (pin "3") (pinfunction "CW_3") (pintype "passive"))
    )
    (net (code "51") (name "Net-(RAD5-CCW)") (class "Default")
      (node (ref "R9") (pin "1") (pinfunction "1_1") (pintype "passive"))
      (node (ref "RAD5") (pin "1") (pinfunction "CCW_1") (pintype "passive"))
      (node (ref "RAD5") (pin "2") (pinfunction "W_2") (pintype "passive"))
    )
    (net (code "52") (name "Net-(RAD6-CW)") (class "Default")
      (node (ref "R10") (pin "2") (pinfunction "2_2") (pintype "passive"))
      (node (ref "RAD6") (pin "2") (pinfunction "W_2") (pintype "passive"))
      (node (ref "RAD6") (pin "3") (pinfunction "CW_3") (pintype "passive"))
    )
    (net (code "53") (name "Net-(RAD7-CCW)") (class "Default")
      (node (ref "R11") (pin "1") (pinfunction "1_1") (pintype "passive"))
      (node (ref "RAD7") (pin "1") (pinfunction "CCW_1") (pintype "passive"))
      (node (ref "RAD7") (pin "2") (pinfunction "W_2") (pintype "passive"))
    )
    (net (code "54") (name "Net-(RAD8-CW)") (class "Default")
      (node (ref "R12") (pin "2") (pinfunction "2_2") (pintype "passive"))
      (node (ref "RAD8") (pin "2") (pinfunction "W_2") (pintype "passive"))
      (node (ref "RAD8") (pin "3") (pinfunction "CW_3") (pintype "passive"))
    )
    (net (code "55") (name "Net-(RAD9-CCW)") (class "Default")
      (node (ref "R13") (pin "1") (pinfunction "1_1") (pintype "passive"))
      (node (ref "RAD9") (pin "1") (pinfunction "CCW_1") (pintype "passive"))
      (node (ref "RAD9") (pin "2") (pinfunction "W_2") (pintype "passive"))
    )
    (net (code "56") (name "Net-(RAD10-CW)") (class "Default")
      (node (ref "R14") (pin "2") (pinfunction "2_2") (pintype "passive"))
      (node (ref "RAD10") (pin "2") (pinfunction "W_2") (pintype "passive"))
      (node (ref "RAD10") (pin "3") (pinfunction "CW_3") (pintype "passive"))
    )
    (net (code "57") (name "Net-(U9-C1+)") (class "Default")
      (node (ref "C4") (pin "1") (pinfunction "1_1") (pintype "passive"))
      (node (ref "U9") (pin "2") (pinfunction "C1+_2") (pintype "passive"))
    )
    (net (code "58") (name "Net-(U9-C1-)") (class "Default")
      (node (ref "C4") (pin "2") (pinfunction "2_2") (pintype "passive"))
      (node (ref "U9") (pin "4") (pinfunction "C1-_4") (pintype "passive"))
    )
    (net (code "59") (name "Net-(U9-FC)") (class "Default")
      (node (ref "R58") (pin "2") (pinfunction "2_2") (pintype "passive"))
      (node (ref "U9") (pin "1") (pinfunction "FC_1") (pintype "passive"))
    )
    (net (code "60") (name "Net-(U9-~{SHD}N)") (class "Default")
      (node (ref "R59") (pin "1") (pinfunction "1_1") (pintype "passive"))
      (node (ref "U9") (pin "7") (pinfunction "~{SHD}N_7") (pintype "passive"))
    )
  )
)
